# IOMOD-v1_0.net
KiCad netlist of a schematic drawn in EAGLE
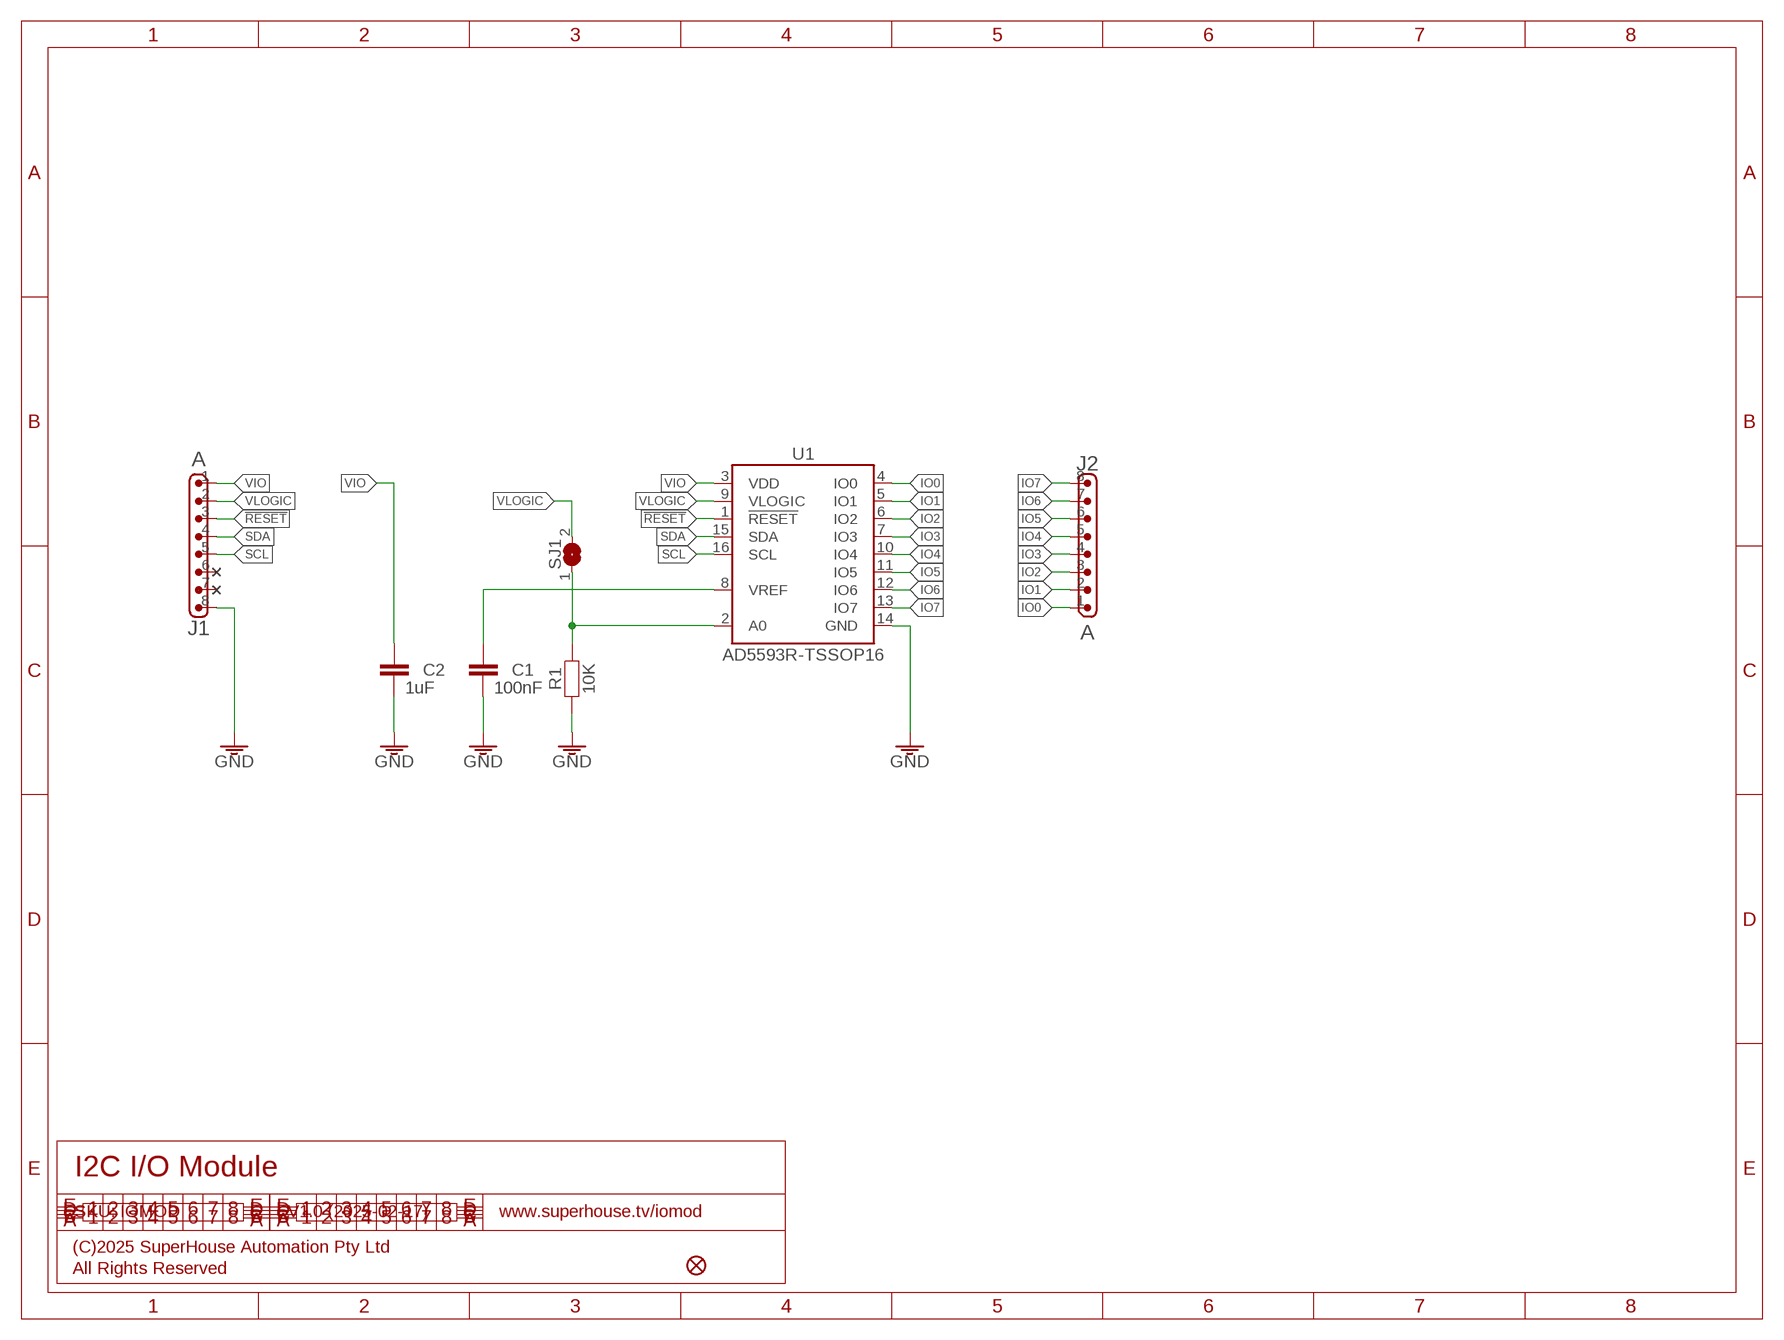
[diagram p0: schematic, sheet 1]

(export (version "E")
  (design (tool "Eeschema 10.0.6"))
  (components
    (comp (ref "C1")
      (value "100nF")
      (footprint "eagle-import:C0603")
      (libsource (lib "eagle-import") (part "CAP0603"))
    )
    (comp (ref "C2")
      (value "1uF")
      (footprint "eagle-import:C0603")
      (libsource (lib "eagle-import") (part "CAP0603"))
    )
    (comp (ref "FID1")
      (value "FIDUCIAL1X2.5")
      (footprint "eagle-import:FIDUCIAL-1X2.5")
      (libsource (lib "eagle-import") (part "FIDUCIAL1X2.5"))
    )
    (comp (ref "J1")
      (value "A")
      (footprint "eagle-import:1X8-2.00-P-BELOW")
      (libsource (lib "eagle-import") (part "M08-2.00-P-BELOW"))
    )
    (comp (ref "J2")
      (value "A")
      (footprint "eagle-import:1X8-2.00-P-BELOW")
      (libsource (lib "eagle-import") (part "M08-2.00-P-BELOW"))
    )
    (comp (ref "R1")
      (value "10K")
      (footprint "eagle-import:R0603")
      (libsource (lib "eagle-import") (part "RESISTOR0603"))
    )
    (comp (ref "SJ1")
      (value "SJ-NORMAL")
      (footprint "eagle-import:SJ")
      (libsource (lib "eagle-import") (part "SJ-NORMAL"))
    )
    (comp (ref "U1")
      (value "AD5593R-TSSOP16")
      (footprint "eagle-import:TSSOP16")
      (libsource (lib "eagle-import") (part "AD5593R-TSSOP16"))
    )
  )
  (nets
    (net (code "1") (name "/~{RESET}") (class "Default")
      (node (ref "J1") (pin "3") (pinfunction "3_3") (pintype "passive"))
      (node (ref "U1") (pin "1") (pinfunction "~{RESET}_1") (pintype "passive"))
    )
    (net (code "2") (name "GND") (class "Default")
      (node (ref "C1") (pin "2") (pinfunction "2_2") (pintype "passive"))
      (node (ref "C2") (pin "2") (pinfunction "2_2") (pintype "passive"))
      (node (ref "J1") (pin "8") (pinfunction "8_8") (pintype "passive"))
      (node (ref "R1") (pin "1") (pinfunction "1_1") (pintype "passive"))
      (node (ref "U1") (pin "14") (pinfunction "GND_14") (pintype "passive"))
    )
    (net (code "3") (name "IO0") (class "Default")
      (node (ref "J2") (pin "1") (pinfunction "1_1") (pintype "passive"))
      (node (ref "U1") (pin "4") (pinfunction "IO0_4") (pintype "passive"))
    )
    (net (code "4") (name "IO1") (class "Default")
      (node (ref "J2") (pin "2") (pinfunction "2_2") (pintype "passive"))
      (node (ref "U1") (pin "5") (pinfunction "IO1_5") (pintype "passive"))
    )
    (net (code "5") (name "IO2") (class "Default")
      (node (ref "J2") (pin "3") (pinfunction "3_3") (pintype "passive"))
      (node (ref "U1") (pin "6") (pinfunction "IO2_6") (pintype "passive"))
    )
    (net (code "6") (name "IO3") (class "Default")
      (node (ref "J2") (pin "4") (pinfunction "4_4") (pintype "passive"))
      (node (ref "U1") (pin "7") (pinfunction "IO3_7") (pintype "passive"))
    )
    (net (code "7") (name "IO4") (class "Default")
      (node (ref "J2") (pin "5") (pinfunction "5_5") (pintype "passive"))
      (node (ref "U1") (pin "10") (pinfunction "IO4_10") (pintype "passive"))
    )
    (net (code "8") (name "IO5") (class "Default")
      (node (ref "J2") (pin "6") (pinfunction "6_6") (pintype "passive"))
      (node (ref "U1") (pin "11") (pinfunction "IO5_11") (pintype "passive"))
    )
    (net (code "9") (name "IO6") (class "Default")
      (node (ref "J2") (pin "7") (pinfunction "7_7") (pintype "passive"))
      (node (ref "U1") (pin "12") (pinfunction "IO6_12") (pintype "passive"))
    )
    (net (code "10") (name "IO7") (class "Default")
      (node (ref "J2") (pin "8") (pinfunction "8_8") (pintype "passive"))
      (node (ref "U1") (pin "13") (pinfunction "IO7_13") (pintype "passive"))
    )
    (net (code "11") (name "Net-(U1-A0)") (class "Default")
      (node (ref "R1") (pin "2") (pinfunction "2_2") (pintype "passive"))
      (node (ref "SJ1") (pin "1") (pinfunction "1_1") (pintype "passive"))
      (node (ref "U1") (pin "2") (pinfunction "A0_2") (pintype "passive"))
    )
    (net (code "12") (name "Net-(U1-VREF)") (class "Default")
      (node (ref "C1") (pin "1") (pinfunction "1_1") (pintype "passive"))
      (node (ref "U1") (pin "8") (pinfunction "VREF_8") (pintype "passive"))
    )
    (net (code "13") (name "SCL") (class "Default")
      (node (ref "J1") (pin "5") (pinfunction "5_5") (pintype "passive"))
      (node (ref "U1") (pin "16") (pinfunction "SCL_16") (pintype "passive"))
    )
    (net (code "14") (name "SDA") (class "Default")
      (node (ref "J1") (pin "4") (pinfunction "4_4") (pintype "passive"))
      (node (ref "U1") (pin "15") (pinfunction "SDA_15") (pintype "passive"))
    )
    (net (code "15") (name "VIO") (class "Default")
      (node (ref "C2") (pin "1") (pinfunction "1_1") (pintype "passive"))
      (node (ref "J1") (pin "1") (pinfunction "1_1") (pintype "passive"))
      (node (ref "U1") (pin "3") (pinfunction "VDD_3") (pintype "passive"))
    )
    (net (code "16") (name "VLOGIC") (class "Default")
      (node (ref "J1") (pin "2") (pinfunction "2_2") (pintype "passive"))
      (node (ref "SJ1") (pin "2") (pinfunction "2_2") (pintype "passive"))
      (node (ref "U1") (pin "9") (pinfunction "VLOGIC_9") (pintype "passive"))
    )
    (net (code "17") (name "unconnected-(J1-Pad6)") (class "Default")
      (node (ref "J1") (pin "6") (pinfunction "6_6") (pintype "passive"))
    )
    (net (code "18") (name "unconnected-(J1-Pad7)") (class "Default")
      (node (ref "J1") (pin "7") (pinfunction "7_7") (pintype "passive"))
    )
  )
)
